# Task0302.net
KiCad netlist of a schematic drawn in Altium Designer
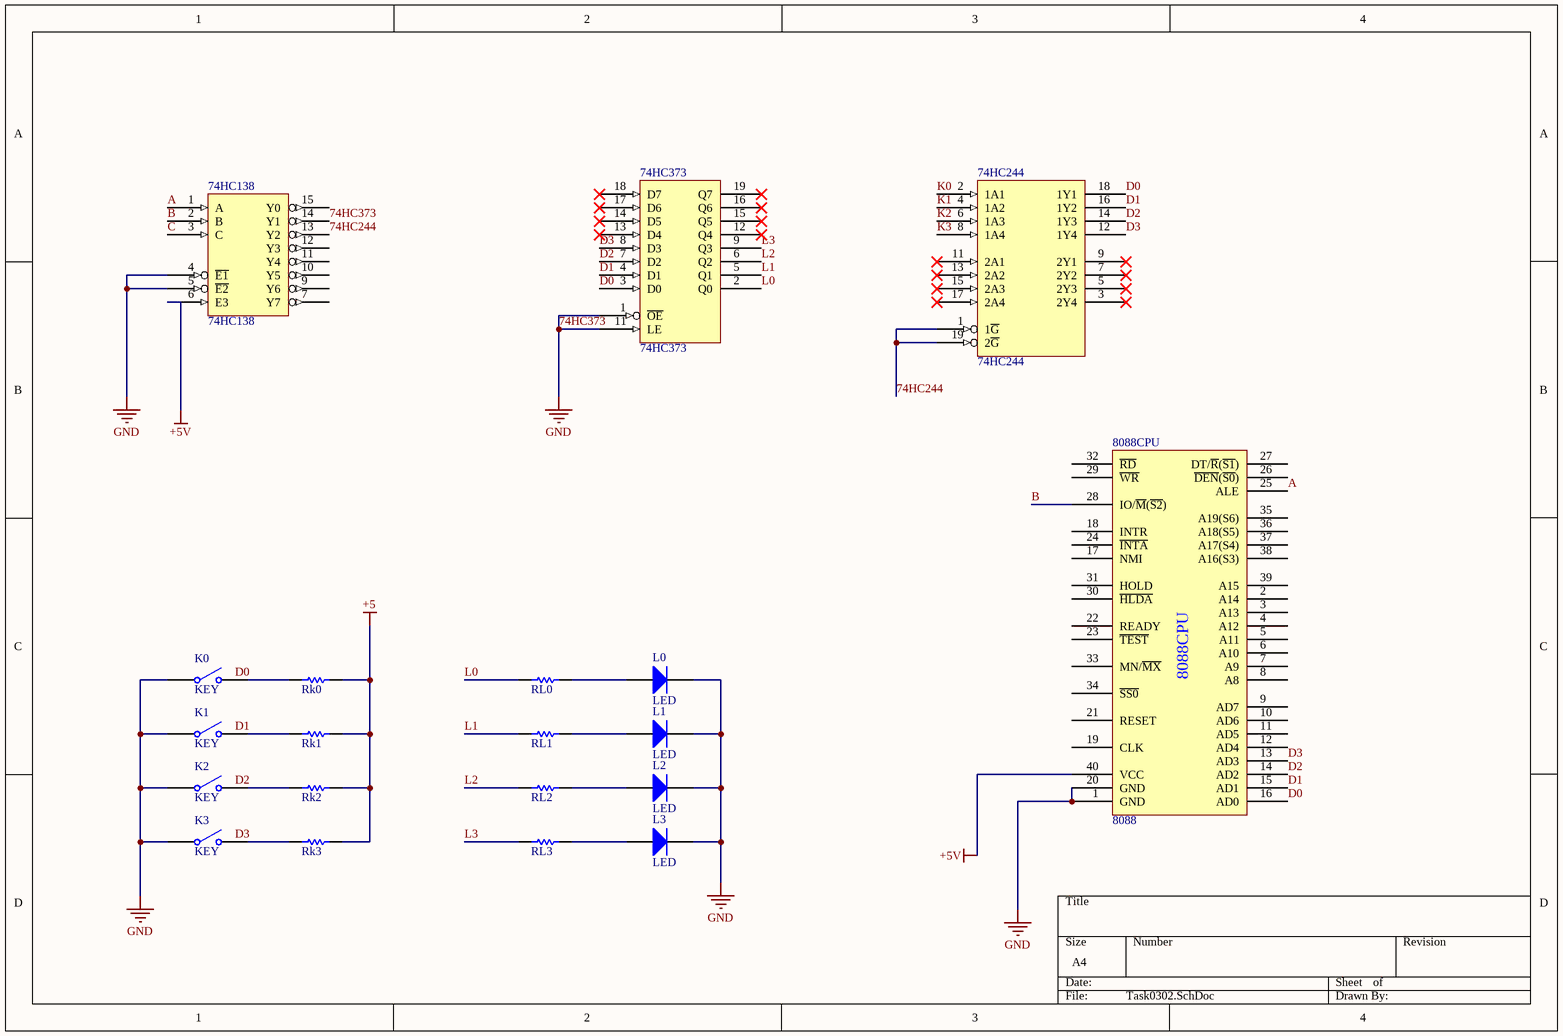
[diagram p0: Task0302.SchDoc]

(export (version "E")
  (design (tool "Eeschema 10.0.6"))
  (components
    (comp (ref "74HC138") (value "74HC138") (libsource (lib "BusAndInterfaceDesign") (part "74HC138")))
    (comp (ref "74HC244") (value "74HC244") (libsource (lib "BusAndInterfaceDesign") (part "74HC244")))
    (comp (ref "74HC373") (value "74HC373") (libsource (lib "BusAndInterfaceDesign") (part "74HC373")))
    (comp (ref "8088CPU") (value "8088") (libsource (lib "BusAndInterfaceDesign") (part "8088")))
    (comp (ref "K0") (value "KEY") (libsource (lib "BusAndInterfaceDesign") (part "KEY")))
    (comp (ref "K1") (value "KEY") (libsource (lib "BusAndInterfaceDesign") (part "KEY")))
    (comp (ref "K2") (value "KEY") (libsource (lib "BusAndInterfaceDesign") (part "KEY")))
    (comp (ref "K3") (value "KEY") (libsource (lib "BusAndInterfaceDesign") (part "KEY")))
    (comp (ref "L0") (value "LED") (libsource (lib "BusAndInterfaceDesign") (part "LED")))
    (comp (ref "L1") (value "LED") (libsource (lib "BusAndInterfaceDesign") (part "LED")))
    (comp (ref "L2") (value "LED") (libsource (lib "BusAndInterfaceDesign") (part "LED")))
    (comp (ref "L3") (value "LED") (libsource (lib "BusAndInterfaceDesign") (part "LED")))
    (comp (ref "Rk0") (value "Res") (libsource (lib "BusAndInterfaceDesign") (part "Res")))
    (comp (ref "Rk1") (value "Res") (libsource (lib "BusAndInterfaceDesign") (part "Res")))
    (comp (ref "Rk2") (value "Res") (libsource (lib "BusAndInterfaceDesign") (part "Res")))
    (comp (ref "Rk3") (value "Res") (libsource (lib "BusAndInterfaceDesign") (part "Res")))
    (comp (ref "RL0") (value "Res") (libsource (lib "BusAndInterfaceDesign") (part "Res")))
    (comp (ref "RL1") (value "Res") (libsource (lib "BusAndInterfaceDesign") (part "Res")))
    (comp (ref "RL2") (value "Res") (libsource (lib "BusAndInterfaceDesign") (part "Res")))
    (comp (ref "RL3") (value "Res") (libsource (lib "BusAndInterfaceDesign") (part "Res")))
  )
  (nets
    (net (code "1") (name "+5") (class "Default")
      (node (ref "Rk0") (pin "2") (pinfunction "2_2") (pintype "passive"))
      (node (ref "Rk1") (pin "2") (pinfunction "2_2") (pintype "passive"))
      (node (ref "Rk2") (pin "2") (pinfunction "2_2") (pintype "passive"))
      (node (ref "Rk3") (pin "2") (pinfunction "2_2") (pintype "passive"))
    )
    (net (code "2") (name "+5V") (class "Default")
      (node (ref "74HC138") (pin "6") (pinfunction "E3_6") (pintype "input"))
      (node (ref "8088CPU") (pin "40") (pinfunction "VCC_40") (pintype "passive"))
    )
    (net (code "3") (name "/74HC244") (class "Default")
      (node (ref "74HC138") (pin "13") (pinfunction "Y2_13") (pintype "output"))
      (node (ref "74HC244") (pin "1") (pinfunction "1~{G}_1") (pintype "input"))
      (node (ref "74HC244") (pin "19") (pinfunction "2~{G}_19") (pintype "input"))
    )
    (net (code "4") (name "/A") (class "Default")
      (node (ref "74HC138") (pin "1") (pinfunction "A_1") (pintype "input"))
      (node (ref "8088CPU") (pin "25") (pinfunction "ALE_25") (pintype "passive"))
    )
    (net (code "5") (name "/B") (class "Default")
      (node (ref "74HC138") (pin "2") (pinfunction "B_2") (pintype "input"))
      (node (ref "8088CPU") (pin "28") (pinfunction "IO/~{M}(~{S2})_28") (pintype "passive"))
    )
    (net (code "6") (name "/C") (class "Default")
      (node (ref "74HC138") (pin "3") (pinfunction "C_3") (pintype "input"))
    )
    (net (code "7") (name "/D0") (class "Default")
      (node (ref "74HC244") (pin "18") (pinfunction "1Y1_18") (pintype "tri_state"))
      (node (ref "74HC373") (pin "3") (pinfunction "D0_3") (pintype "input"))
      (node (ref "8088CPU") (pin "16") (pinfunction "AD0_16") (pintype "passive"))
    )
    (net (code "8") (name "/D1") (class "Default")
      (node (ref "74HC244") (pin "16") (pinfunction "1Y2_16") (pintype "tri_state"))
      (node (ref "74HC373") (pin "4") (pinfunction "D1_4") (pintype "input"))
      (node (ref "8088CPU") (pin "15") (pinfunction "AD1_15") (pintype "passive"))
    )
    (net (code "9") (name "/D2") (class "Default")
      (node (ref "74HC244") (pin "14") (pinfunction "1Y3_14") (pintype "tri_state"))
      (node (ref "74HC373") (pin "7") (pinfunction "D2_7") (pintype "input"))
      (node (ref "8088CPU") (pin "14") (pinfunction "AD2_14") (pintype "passive"))
    )
    (net (code "10") (name "/D3") (class "Default")
      (node (ref "74HC244") (pin "12") (pinfunction "1Y4_12") (pintype "tri_state"))
      (node (ref "74HC373") (pin "8") (pinfunction "D3_8") (pintype "input"))
      (node (ref "8088CPU") (pin "13") (pinfunction "AD3_13") (pintype "passive"))
    )
    (net (code "11") (name "/K0") (class "Default")
      (node (ref "74HC244") (pin "2") (pinfunction "1A1_2") (pintype "input"))
    )
    (net (code "12") (name "/K1") (class "Default")
      (node (ref "74HC244") (pin "4") (pinfunction "1A2_4") (pintype "input"))
    )
    (net (code "13") (name "/K2") (class "Default")
      (node (ref "74HC244") (pin "6") (pinfunction "1A3_6") (pintype "input"))
    )
    (net (code "14") (name "/K3") (class "Default")
      (node (ref "74HC244") (pin "8") (pinfunction "1A4_8") (pintype "input"))
    )
    (net (code "15") (name "/L0") (class "Default")
      (node (ref "74HC373") (pin "2") (pinfunction "Q0_2") (pintype "tri_state"))
      (node (ref "RL0") (pin "1") (pinfunction "1_1") (pintype "passive"))
    )
    (net (code "16") (name "/L1") (class "Default")
      (node (ref "74HC373") (pin "5") (pinfunction "Q1_5") (pintype "tri_state"))
      (node (ref "RL1") (pin "1") (pinfunction "1_1") (pintype "passive"))
    )
    (net (code "17") (name "/L2") (class "Default")
      (node (ref "74HC373") (pin "6") (pinfunction "Q2_6") (pintype "tri_state"))
      (node (ref "RL2") (pin "1") (pinfunction "1_1") (pintype "passive"))
    )
    (net (code "18") (name "/L3") (class "Default")
      (node (ref "74HC373") (pin "9") (pinfunction "Q3_9") (pintype "tri_state"))
      (node (ref "RL3") (pin "1") (pinfunction "1_1") (pintype "passive"))
    )
    (net (code "19") (name "GND") (class "Default")
      (node (ref "74HC138") (pin "14") (pinfunction "Y1_14") (pintype "output"))
      (node (ref "74HC138") (pin "4") (pinfunction "~{E1}_4") (pintype "input"))
      (node (ref "74HC138") (pin "5") (pinfunction "~{E2}_5") (pintype "input"))
      (node (ref "74HC373") (pin "1") (pinfunction "~{OE}_1") (pintype "input"))
      (node (ref "74HC373") (pin "11") (pinfunction "LE_11") (pintype "input"))
      (node (ref "8088CPU") (pin "1") (pinfunction "GND_1") (pintype "passive"))
      (node (ref "8088CPU") (pin "20") (pinfunction "GND_20") (pintype "passive"))
      (node (ref "K0") (pin "1") (pinfunction "COMMON_1") (pintype "passive"))
      (node (ref "K1") (pin "1") (pinfunction "COMMON_1") (pintype "passive"))
      (node (ref "K2") (pin "1") (pinfunction "COMMON_1") (pintype "passive"))
      (node (ref "K3") (pin "1") (pinfunction "COMMON_1") (pintype "passive"))
      (node (ref "L0") (pin "2") (pinfunction "K_2") (pintype "passive"))
      (node (ref "L1") (pin "2") (pinfunction "K_2") (pintype "passive"))
      (node (ref "L2") (pin "2") (pinfunction "K_2") (pintype "passive"))
      (node (ref "L3") (pin "2") (pinfunction "K_2") (pintype "passive"))
    )
    (net (code "20") (name "Net-(K0-NO)") (class "Default")
      (node (ref "K0") (pin "2") (pinfunction "NO_2") (pintype "passive"))
      (node (ref "Rk0") (pin "1") (pinfunction "1_1") (pintype "passive"))
    )
    (net (code "21") (name "Net-(K1-NO)") (class "Default")
      (node (ref "K1") (pin "2") (pinfunction "NO_2") (pintype "passive"))
      (node (ref "Rk1") (pin "1") (pinfunction "1_1") (pintype "passive"))
    )
    (net (code "22") (name "Net-(K2-NO)") (class "Default")
      (node (ref "K2") (pin "2") (pinfunction "NO_2") (pintype "passive"))
      (node (ref "Rk2") (pin "1") (pinfunction "1_1") (pintype "passive"))
    )
    (net (code "23") (name "Net-(K3-NO)") (class "Default")
      (node (ref "K3") (pin "2") (pinfunction "NO_2") (pintype "passive"))
      (node (ref "Rk3") (pin "1") (pinfunction "1_1") (pintype "passive"))
    )
    (net (code "24") (name "Net-(L0-A)") (class "Default")
      (node (ref "L0") (pin "1") (pinfunction "A_1") (pintype "passive"))
      (node (ref "RL0") (pin "2") (pinfunction "2_2") (pintype "passive"))
    )
    (net (code "25") (name "Net-(L1-A)") (class "Default")
      (node (ref "L1") (pin "1") (pinfunction "A_1") (pintype "passive"))
      (node (ref "RL1") (pin "2") (pinfunction "2_2") (pintype "passive"))
    )
    (net (code "26") (name "Net-(L2-A)") (class "Default")
      (node (ref "L2") (pin "1") (pinfunction "A_1") (pintype "passive"))
      (node (ref "RL2") (pin "2") (pinfunction "2_2") (pintype "passive"))
    )
    (net (code "27") (name "Net-(L3-A)") (class "Default")
      (node (ref "L3") (pin "1") (pinfunction "A_1") (pintype "passive"))
      (node (ref "RL3") (pin "2") (pinfunction "2_2") (pintype "passive"))
    )
    (net (code "28") (name "unconnected-(74HC138-Y0-Pad15)") (class "Default")
      (node (ref "74HC138") (pin "15") (pinfunction "Y0_15") (pintype "output"))
    )
    (net (code "29") (name "unconnected-(74HC138-Y3-Pad12)") (class "Default")
      (node (ref "74HC138") (pin "12") (pinfunction "Y3_12") (pintype "output"))
    )
    (net (code "30") (name "unconnected-(74HC138-Y4-Pad11)") (class "Default")
      (node (ref "74HC138") (pin "11") (pinfunction "Y4_11") (pintype "output"))
    )
    (net (code "31") (name "unconnected-(74HC138-Y5-Pad10)") (class "Default")
      (node (ref "74HC138") (pin "10") (pinfunction "Y5_10") (pintype "output"))
    )
    (net (code "32") (name "unconnected-(74HC138-Y6-Pad9)") (class "Default")
      (node (ref "74HC138") (pin "9") (pinfunction "Y6_9") (pintype "output"))
    )
    (net (code "33") (name "unconnected-(74HC138-Y7-Pad7)") (class "Default")
      (node (ref "74HC138") (pin "7") (pinfunction "Y7_7") (pintype "output"))
    )
    (net (code "34") (name "unconnected-(74HC244-2A1-Pad11)") (class "Default")
      (node (ref "74HC244") (pin "11") (pinfunction "2A1_11") (pintype "input+no_connect"))
    )
    (net (code "35") (name "unconnected-(74HC244-2A2-Pad13)") (class "Default")
      (node (ref "74HC244") (pin "13") (pinfunction "2A2_13") (pintype "input+no_connect"))
    )
    (net (code "36") (name "unconnected-(74HC244-2A3-Pad15)") (class "Default")
      (node (ref "74HC244") (pin "15") (pinfunction "2A3_15") (pintype "input+no_connect"))
    )
    (net (code "37") (name "unconnected-(74HC244-2A4-Pad17)") (class "Default")
      (node (ref "74HC244") (pin "17") (pinfunction "2A4_17") (pintype "input+no_connect"))
    )
    (net (code "38") (name "unconnected-(74HC244-2Y1-Pad9)") (class "Default")
      (node (ref "74HC244") (pin "9") (pinfunction "2Y1_9") (pintype "tri_state+no_connect"))
    )
    (net (code "39") (name "unconnected-(74HC244-2Y2-Pad7)") (class "Default")
      (node (ref "74HC244") (pin "7") (pinfunction "2Y2_7") (pintype "tri_state+no_connect"))
    )
    (net (code "40") (name "unconnected-(74HC244-2Y3-Pad5)") (class "Default")
      (node (ref "74HC244") (pin "5") (pinfunction "2Y3_5") (pintype "tri_state+no_connect"))
    )
    (net (code "41") (name "unconnected-(74HC244-2Y4-Pad3)") (class "Default")
      (node (ref "74HC244") (pin "3") (pinfunction "2Y4_3") (pintype "tri_state+no_connect"))
    )
    (net (code "42") (name "unconnected-(74HC373-D4-Pad13)") (class "Default")
      (node (ref "74HC373") (pin "13") (pinfunction "D4_13") (pintype "input+no_connect"))
    )
    (net (code "43") (name "unconnected-(74HC373-D5-Pad14)") (class "Default")
      (node (ref "74HC373") (pin "14") (pinfunction "D5_14") (pintype "input+no_connect"))
    )
    (net (code "44") (name "unconnected-(74HC373-D6-Pad17)") (class "Default")
      (node (ref "74HC373") (pin "17") (pinfunction "D6_17") (pintype "input+no_connect"))
    )
    (net (code "45") (name "unconnected-(74HC373-D7-Pad18)") (class "Default")
      (node (ref "74HC373") (pin "18") (pinfunction "D7_18") (pintype "input+no_connect"))
    )
    (net (code "46") (name "unconnected-(74HC373-Q4-Pad12)") (class "Default")
      (node (ref "74HC373") (pin "12") (pinfunction "Q4_12") (pintype "tri_state+no_connect"))
    )
    (net (code "47") (name "unconnected-(74HC373-Q5-Pad15)") (class "Default")
      (node (ref "74HC373") (pin "15") (pinfunction "Q5_15") (pintype "tri_state+no_connect"))
    )
    (net (code "48") (name "unconnected-(74HC373-Q6-Pad16)") (class "Default")
      (node (ref "74HC373") (pin "16") (pinfunction "Q6_16") (pintype "tri_state+no_connect"))
    )
    (net (code "49") (name "unconnected-(74HC373-Q7-Pad19)") (class "Default")
      (node (ref "74HC373") (pin "19") (pinfunction "Q7_19") (pintype "tri_state+no_connect"))
    )
    (net (code "50") (name "unconnected-(8088CPU-A8-Pad8)") (class "Default")
      (node (ref "8088CPU") (pin "8") (pinfunction "A8_8") (pintype "passive"))
    )
    (net (code "51") (name "unconnected-(8088CPU-A9-Pad7)") (class "Default")
      (node (ref "8088CPU") (pin "7") (pinfunction "A9_7") (pintype "passive"))
    )
    (net (code "52") (name "unconnected-(8088CPU-A10-Pad6)") (class "Default")
      (node (ref "8088CPU") (pin "6") (pinfunction "A10_6") (pintype "passive"))
    )
    (net (code "53") (name "unconnected-(8088CPU-A11-Pad5)") (class "Default")
      (node (ref "8088CPU") (pin "5") (pinfunction "A11_5") (pintype "passive"))
    )
    (net (code "54") (name "unconnected-(8088CPU-A12-Pad4)") (class "Default")
      (node (ref "8088CPU") (pin "4") (pinfunction "A12_4") (pintype "passive"))
    )
    (net (code "55") (name "unconnected-(8088CPU-A13-Pad3)") (class "Default")
      (node (ref "8088CPU") (pin "3") (pinfunction "A13_3") (pintype "passive"))
    )
    (net (code "56") (name "unconnected-(8088CPU-A14-Pad2)") (class "Default")
      (node (ref "8088CPU") (pin "2") (pinfunction "A14_2") (pintype "passive"))
    )
    (net (code "57") (name "unconnected-(8088CPU-A15-Pad39)") (class "Default")
      (node (ref "8088CPU") (pin "39") (pinfunction "A15_39") (pintype "passive"))
    )
    (net (code "58") (name "unconnected-(8088CPU-A16(S3)-Pad38)") (class "Default")
      (node (ref "8088CPU") (pin "38") (pinfunction "A16(S3)_38") (pintype "passive"))
    )
    (net (code "59") (name "unconnected-(8088CPU-A17(S4)-Pad37)") (class "Default")
      (node (ref "8088CPU") (pin "37") (pinfunction "A17(S4)_37") (pintype "passive"))
    )
    (net (code "60") (name "unconnected-(8088CPU-A18(S5)-Pad36)") (class "Default")
      (node (ref "8088CPU") (pin "36") (pinfunction "A18(S5)_36") (pintype "passive"))
    )
    (net (code "61") (name "unconnected-(8088CPU-A19(S6)-Pad35)") (class "Default")
      (node (ref "8088CPU") (pin "35") (pinfunction "A19(S6)_35") (pintype "passive"))
    )
    (net (code "62") (name "unconnected-(8088CPU-AD4-Pad12)") (class "Default")
      (node (ref "8088CPU") (pin "12") (pinfunction "AD4_12") (pintype "passive"))
    )
    (net (code "63") (name "unconnected-(8088CPU-AD5-Pad11)") (class "Default")
      (node (ref "8088CPU") (pin "11") (pinfunction "AD5_11") (pintype "passive"))
    )
    (net (code "64") (name "unconnected-(8088CPU-AD6-Pad10)") (class "Default")
      (node (ref "8088CPU") (pin "10") (pinfunction "AD6_10") (pintype "passive"))
    )
    (net (code "65") (name "unconnected-(8088CPU-AD7-Pad9)") (class "Default")
      (node (ref "8088CPU") (pin "9") (pinfunction "AD7_9") (pintype "passive"))
    )
    (net (code "66") (name "unconnected-(8088CPU-CLK-Pad19)") (class "Default")
      (node (ref "8088CPU") (pin "19") (pinfunction "CLK_19") (pintype "passive"))
    )
    (net (code "67") (name "unconnected-(8088CPU-DT{slash}~{R}(~{S1})-Pad27)") (class "Default")
      (node (ref "8088CPU") (pin "27") (pinfunction "DT/~{R}(~{S1})_27") (pintype "passive"))
    )
    (net (code "68") (name "unconnected-(8088CPU-HOLD-Pad31)") (class "Default")
      (node (ref "8088CPU") (pin "31") (pinfunction "HOLD_31") (pintype "passive"))
    )
    (net (code "69") (name "unconnected-(8088CPU-INTR-Pad18)") (class "Default")
      (node (ref "8088CPU") (pin "18") (pinfunction "INTR_18") (pintype "passive"))
    )
    (net (code "70") (name "unconnected-(8088CPU-MN{slash}~{MX}-Pad33)") (class "Default")
      (node (ref "8088CPU") (pin "33") (pinfunction "MN/~{MX}_33") (pintype "passive"))
    )
    (net (code "71") (name "unconnected-(8088CPU-NMI-Pad17)") (class "Default")
      (node (ref "8088CPU") (pin "17") (pinfunction "NMI_17") (pintype "passive"))
    )
    (net (code "72") (name "unconnected-(8088CPU-READY-Pad22)") (class "Default")
      (node (ref "8088CPU") (pin "22") (pinfunction "READY_22") (pintype "passive"))
    )
    (net (code "73") (name "unconnected-(8088CPU-RESET-Pad21)") (class "Default")
      (node (ref "8088CPU") (pin "21") (pinfunction "RESET_21") (pintype "passive"))
    )
    (net (code "74") (name "unconnected-(8088CPU-~{DEN}(~{S0})-Pad26)") (class "Default")
      (node (ref "8088CPU") (pin "26") (pinfunction "~{DEN}(~{S0})_26") (pintype "passive"))
    )
    (net (code "75") (name "unconnected-(8088CPU-~{HLDA}-Pad30)") (class "Default")
      (node (ref "8088CPU") (pin "30") (pinfunction "~{HLDA}_30") (pintype "passive"))
    )
    (net (code "76") (name "unconnected-(8088CPU-~{INTA}-Pad24)") (class "Default")
      (node (ref "8088CPU") (pin "24") (pinfunction "~{INTA}_24") (pintype "passive"))
    )
    (net (code "77") (name "unconnected-(8088CPU-~{RD}-Pad32)") (class "Default")
      (node (ref "8088CPU") (pin "32") (pinfunction "~{RD}_32") (pintype "passive"))
    )
    (net (code "78") (name "unconnected-(8088CPU-~{SS0}-Pad34)") (class "Default")
      (node (ref "8088CPU") (pin "34") (pinfunction "~{SS0}_34") (pintype "passive"))
    )
    (net (code "79") (name "unconnected-(8088CPU-~{TEST}-Pad23)") (class "Default")
      (node (ref "8088CPU") (pin "23") (pinfunction "~{TEST}_23") (pintype "passive"))
    )
    (net (code "80") (name "unconnected-(8088CPU-~{WR}-Pad29)") (class "Default")
      (node (ref "8088CPU") (pin "29") (pinfunction "~{WR}_29") (pintype "passive"))
    )
  )
)
